# loicpinuela1.net
KiCad netlist of a schematic drawn in Altium Designer
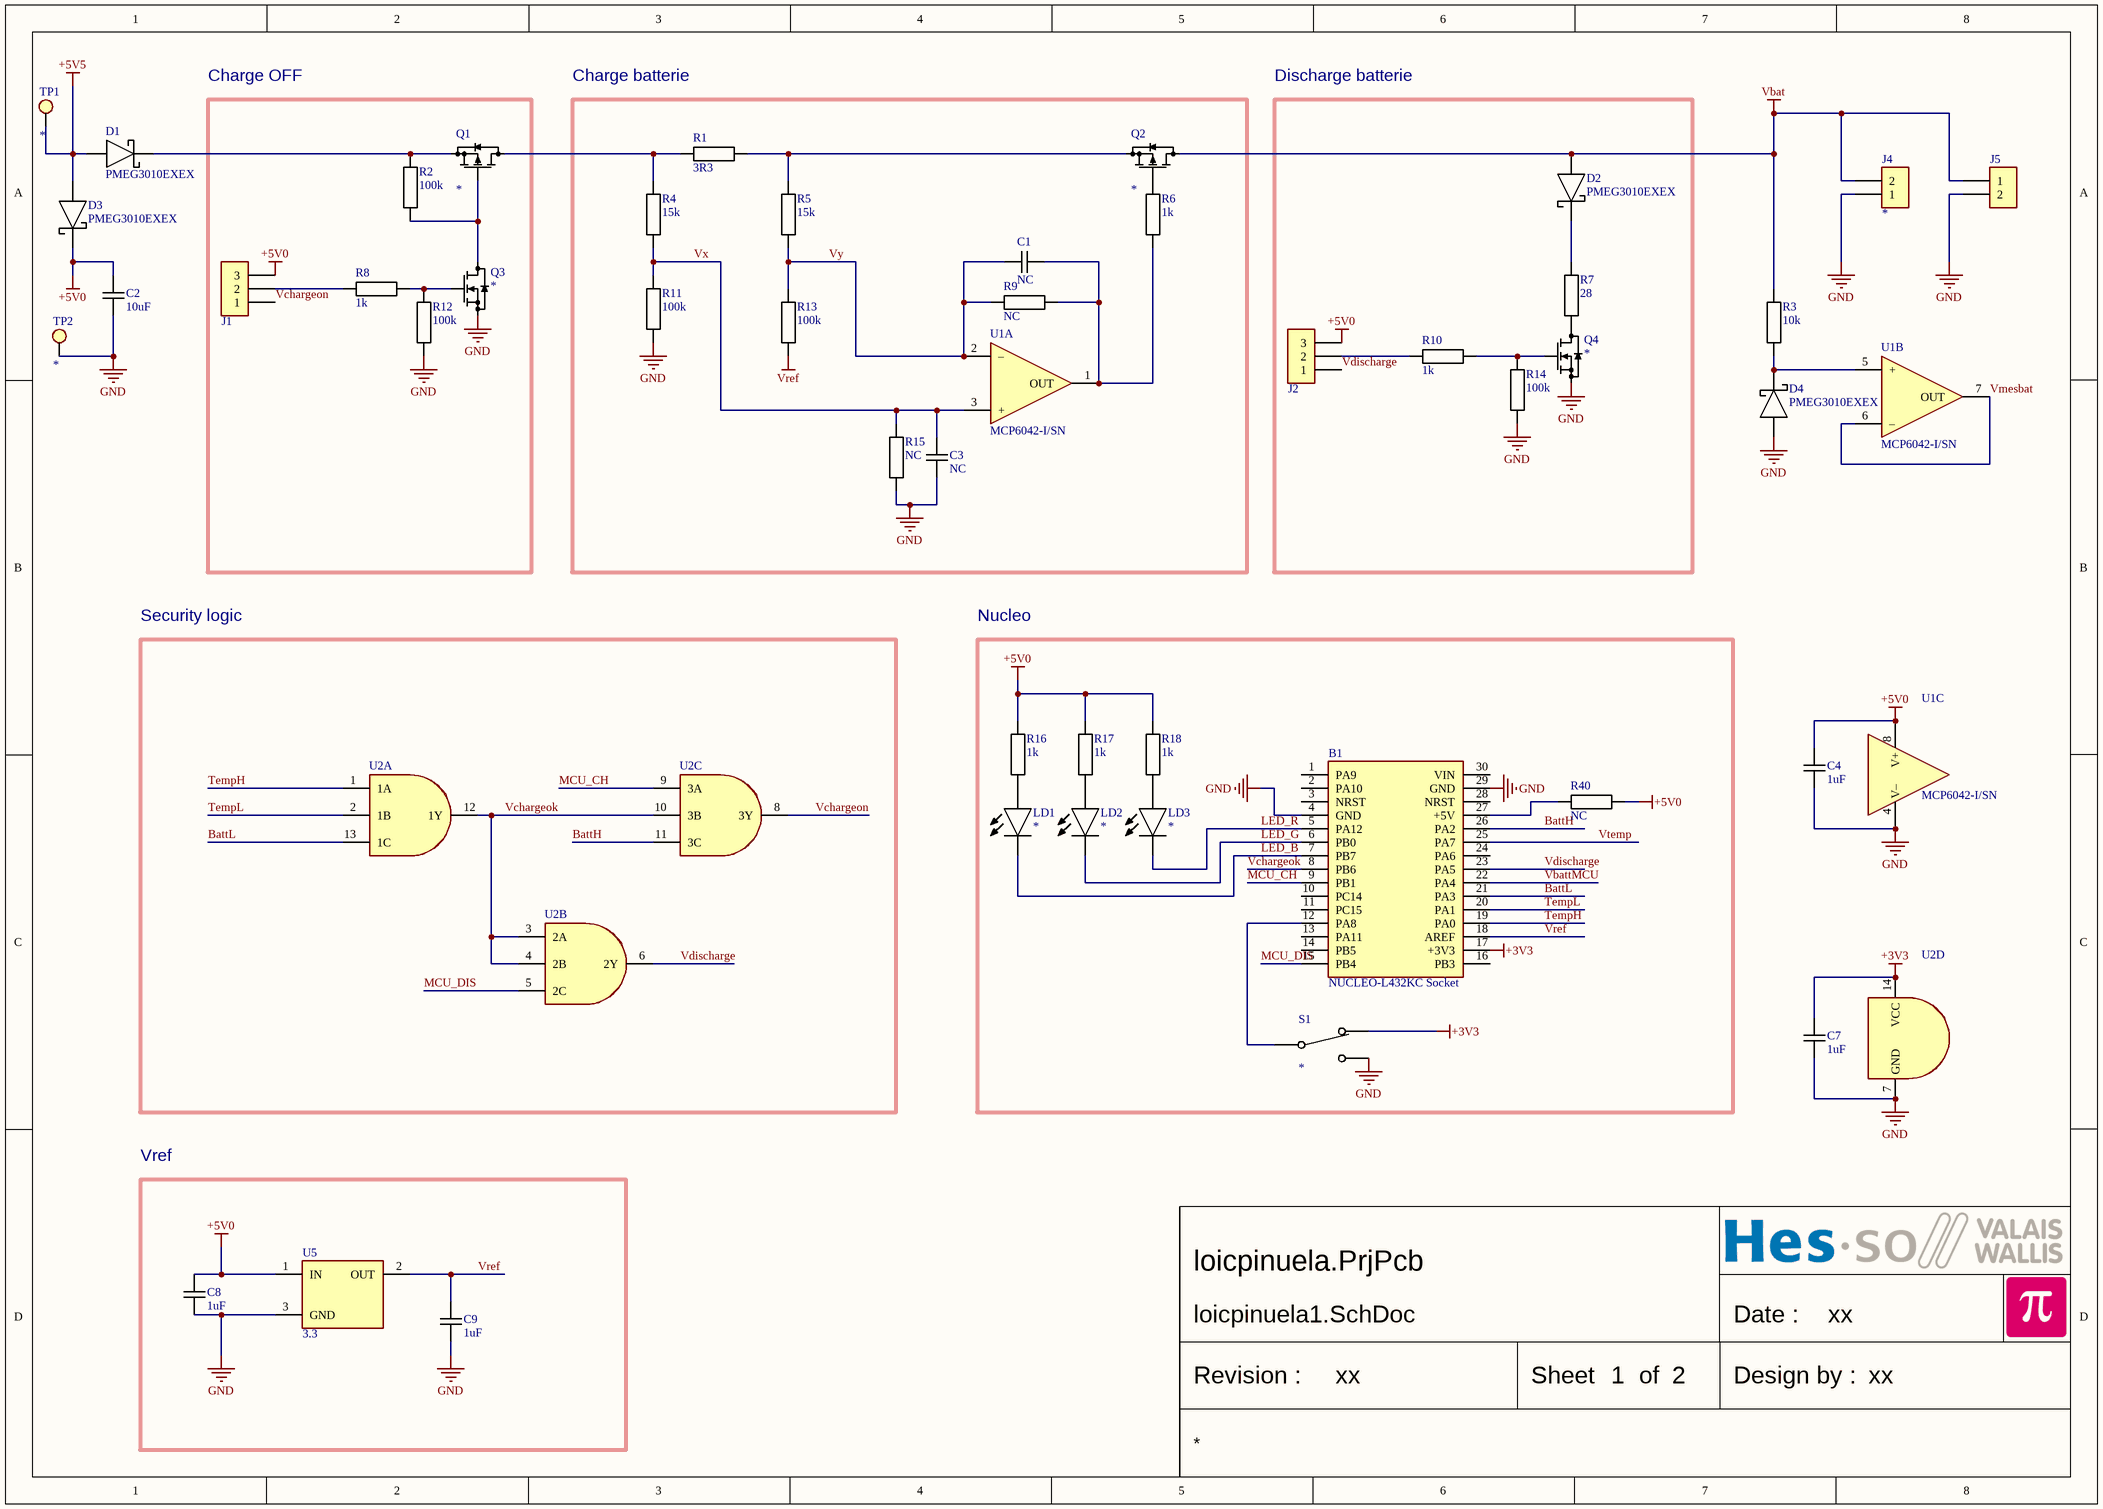
[diagram p0: loicpinuela1.SchDoc]

(export (version "E")
  (design (tool "Eeschema 10.0.6"))
  (components
    (comp (ref "B1")
      (value "NUCLEO-L432KC Socket")
      (footprint "NUCLEO-L432KC Socket")
      (description "ARM Cortex based board")
      (libsource (lib "DevBoard") (part "NUCLEO-L432KC Socket"))
    )
    (comp (ref "C1")
      (value "NC")
      (footprint "CAPACITOR 2012 REFLOW")
      (description "Capacitor")
      (libsource (lib "Capacitor") (part "Capacitor"))
    )
    (comp (ref "C2")
      (value "10uF")
      (footprint "CAPACITOR 2012 REFLOW")
      (description "Capacitor")
      (libsource (lib "Capacitor") (part "Capacitor"))
    )
    (comp (ref "C3")
      (value "NC")
      (footprint "CAPACITOR 2012 REFLOW")
      (description "Capacitor")
      (libsource (lib "Capacitor") (part "Capacitor"))
    )
    (comp (ref "C4")
      (value "1uF")
      (footprint "CAPACITOR 2012 REFLOW")
      (description "Capacitor")
      (libsource (lib "Capacitor") (part "Capacitor"))
    )
    (comp (ref "C7")
      (value "1uF")
      (footprint "CAPACITOR 2012 REFLOW")
      (description "Capacitor")
      (libsource (lib "Capacitor") (part "Capacitor"))
    )
    (comp (ref "C8")
      (value "1uF")
      (footprint "CAPACITOR 2012 REFLOW")
      (description "Capacitor")
      (libsource (lib "Capacitor") (part "Capacitor"))
    )
    (comp (ref "C9")
      (value "1uF")
      (footprint "CAPACITOR 2012 REFLOW")
      (description "Capacitor")
      (libsource (lib "Capacitor") (part "Capacitor"))
    )
    (comp (ref "D1")
      (value "PMEG3010EXEX")
      (footprint "DIODE SOD123-FL REFLOW")
      (description "Diode Schottky generic 2 Leads")
      (libsource (lib "Diode") (part "DIODE SCHOTTKY"))
    )
    (comp (ref "D2")
      (value "PMEG3010EXEX")
      (footprint "DIODE SOD123-FL REFLOW")
      (description "Diode Schottky generic 2 Leads")
      (libsource (lib "Diode") (part "DIODE SCHOTTKY"))
    )
    (comp (ref "D3")
      (value "PMEG3010EXEX")
      (footprint "DIODE SOD123-FL REFLOW")
      (description "Diode Schottky generic 2 Leads")
      (libsource (lib "Diode") (part "DIODE SCHOTTKY"))
    )
    (comp (ref "D4")
      (value "PMEG3010EXEX")
      (footprint "DIODE SOD123-FL REFLOW")
      (description "Diode Schottky generic 2 Leads")
      (libsource (lib "Diode") (part "DIODE SCHOTTKY"))
    )
    (comp (ref "J1")
      (value "*")
      (footprint "PinHeader1x3 P2.54")
      (description "Plug connector")
      (libsource (lib "PinHeader") (part "PinHeader1x3"))
    )
    (comp (ref "J2")
      (value "*")
      (footprint "PinHeader1x3 P2.54")
      (description "Plug connector")
      (libsource (lib "PinHeader") (part "PinHeader1x3"))
    )
    (comp (ref "J4")
      (value "*")
      (footprint "WE 691411810002")
      (description "PCB terminal block")
      (libsource (lib "Header") (part "Header2"))
    )
    (comp (ref "J5")
      (value "~")
      (footprint "Socket1x2 P2.54")
      (description "Receptacle connector")
      (libsource (lib "PinHeader") (part "Socket1x2"))
    )
    (comp (ref "LD1")
      (value "*")
      (footprint "LED 3216 REFLOW")
      (description "LED generic")
      (libsource (lib "Diode") (part "LED"))
    )
    (comp (ref "LD2")
      (value "*")
      (footprint "LED 3216 REFLOW")
      (description "LED generic")
      (libsource (lib "Diode") (part "LED"))
    )
    (comp (ref "LD3")
      (value "*")
      (footprint "LED 3216 REFLOW")
      (description "LED generic")
      (libsource (lib "Diode") (part "LED"))
    )
    (comp (ref "Q1")
      (value "*")
      (footprint "SOT23 P0.95 C1.6x3.0 H1.3")
      (description "Generic MOS-P")
      (libsource (lib "Transistor") (part "MOS-P SOT23 G-S-D"))
    )
    (comp (ref "Q2")
      (value "*")
      (footprint "SOT23 P0.95 C1.6x3.0 H1.3")
      (description "Generic MOS-P")
      (libsource (lib "Transistor") (part "MOS-P SOT23 G-S-D"))
    )
    (comp (ref "Q3")
      (value "*")
      (footprint "SOT23 P0.95 C1.6x3.0 H1.3")
      (description "Generic MOS-N")
      (libsource (lib "Transistor") (part "MOS-N SOT23 G-S-D"))
    )
    (comp (ref "Q4")
      (value "*")
      (footprint "SOT23 P0.95 C1.6x3.0 H1.3")
      (description "Generic MOS-N")
      (libsource (lib "Transistor") (part "MOS-N SOT23 G-S-D"))
    )
    (comp (ref "R1")
      (value "3R3")
      (footprint "RESISTOR 2012 REFLOW")
      (description "Resistor")
      (libsource (lib "Resistor") (part "Resistor"))
    )
    (comp (ref "R2")
      (value "100k")
      (footprint "RESISTOR 2012 REFLOW")
      (description "Resistor")
      (fields (field (name "TOLERANCE") "1%"))
      (libsource (lib "Resistor") (part "Resistor"))
    )
    (comp (ref "R3")
      (value "10k")
      (footprint "RESISTOR 2012 REFLOW")
      (description "Resistor")
      (fields (field (name "TOLERANCE") "1%"))
      (libsource (lib "Resistor") (part "Resistor"))
    )
    (comp (ref "R4")
      (value "15k")
      (footprint "RESISTOR 2012 REFLOW")
      (description "Resistor")
      (fields (field (name "TOLERANCE") "1%"))
      (libsource (lib "Resistor") (part "Resistor"))
    )
    (comp (ref "R5")
      (value "15k")
      (footprint "RESISTOR 2012 REFLOW")
      (description "Resistor")
      (fields (field (name "TOLERANCE") "1%"))
      (libsource (lib "Resistor") (part "Resistor"))
    )
    (comp (ref "R6")
      (value "1k")
      (footprint "RESISTOR 2012 REFLOW")
      (description "Resistor")
      (fields (field (name "TOLERANCE") "1%"))
      (libsource (lib "Resistor") (part "Resistor"))
    )
    (comp (ref "R7")
      (value "28")
      (footprint "RESISTOR 2012 REFLOW")
      (description "Resistor")
      (fields (field (name "TOLERANCE") "1%"))
      (libsource (lib "Resistor") (part "Resistor"))
    )
    (comp (ref "R8")
      (value "1k")
      (footprint "RESISTOR 2012 REFLOW")
      (description "Resistor")
      (fields (field (name "TOLERANCE") "1%"))
      (libsource (lib "Resistor") (part "Resistor"))
    )
    (comp (ref "R9")
      (value "NC")
      (footprint "RESISTOR 2012 REFLOW")
      (description "Resistor")
      (libsource (lib "Resistor") (part "Resistor"))
    )
    (comp (ref "R10")
      (value "1k")
      (footprint "RESISTOR 2012 REFLOW")
      (description "Resistor")
      (fields (field (name "TOLERANCE") "1%"))
      (libsource (lib "Resistor") (part "Resistor"))
    )
    (comp (ref "R11")
      (value "100k")
      (footprint "RESISTOR 2012 REFLOW")
      (description "Resistor")
      (fields (field (name "TOLERANCE") "1%"))
      (libsource (lib "Resistor") (part "Resistor"))
    )
    (comp (ref "R12")
      (value "100k")
      (footprint "RESISTOR 2012 REFLOW")
      (description "Resistor")
      (fields (field (name "TOLERANCE") "1%"))
      (libsource (lib "Resistor") (part "Resistor"))
    )
    (comp (ref "R13")
      (value "100k")
      (footprint "RESISTOR 2012 REFLOW")
      (description "Resistor")
      (fields (field (name "TOLERANCE") "1%"))
      (libsource (lib "Resistor") (part "Resistor"))
    )
    (comp (ref "R14")
      (value "100k")
      (footprint "RESISTOR 2012 REFLOW")
      (description "Resistor")
      (fields (field (name "TOLERANCE") "1%"))
      (libsource (lib "Resistor") (part "Resistor"))
    )
    (comp (ref "R15")
      (value "NC")
      (footprint "RESISTOR 2012 REFLOW")
      (description "Resistor")
      (libsource (lib "Resistor") (part "Resistor"))
    )
    (comp (ref "R16")
      (value "1k")
      (footprint "RESISTOR 2012 REFLOW")
      (description "Resistor")
      (fields (field (name "TOLERANCE") "1%"))
      (libsource (lib "Resistor") (part "Resistor"))
    )
    (comp (ref "R17")
      (value "1k")
      (footprint "RESISTOR 2012 REFLOW")
      (description "Resistor")
      (fields (field (name "TOLERANCE") "1%"))
      (libsource (lib "Resistor") (part "Resistor"))
    )
    (comp (ref "R18")
      (value "1k")
      (footprint "RESISTOR 2012 REFLOW")
      (description "Resistor")
      (fields (field (name "TOLERANCE") "1%"))
      (libsource (lib "Resistor") (part "Resistor"))
    )
    (comp (ref "R40")
      (value "NC")
      (footprint "RESISTOR 2012 REFLOW")
      (description "Resistor")
      (libsource (lib "Resistor") (part "Resistor"))
    )
    (comp (ref "S1")
      (value "*")
      (footprint "SLIDE SWITCH Knitter MFP120")
      (description "Slide Switch 1Pole ON-ON")
      (fields (field (name "ALTIUM_VALUE") "*"))
      (libsource (lib "Button") (part "Slide Switch 1Pole ON-ON"))
    )
    (comp (ref "TP1")
      (value "*")
      (footprint "Hole 0.8 D1.5")
      (description "Hole")
      (libsource (lib "Testpoint") (part "Hole"))
    )
    (comp (ref "TP2")
      (value "*")
      (footprint "Hole 0.8 D1.5")
      (description "Hole")
      (libsource (lib "Testpoint") (part "Hole"))
    )
    (comp (ref "U1")
      (value "MCP6042-I/SN")
      (footprint "SO8 P1.27 C4.0X5.0 H1.75")
      (description "Generic dual OPA 8 pins")
      (libsource (lib "Amplifier") (part "OPA DUAL"))
    )
    (comp (ref "U2")
      (value "~")
      (footprint "SO14 P1.27 C4.0X8.8 H1.75")
      (description "GATE AND 3X  TRIPLE INPUT 14P")
      (libsource (lib "IntegratedCircuit") (part "GATE AND 3X  TRIPLE INPUT 14P"))
    )
    (comp (ref "U5")
      (value "3.3")
      (footprint "SOT23 P0.95 C1.6x3.0 H1.3")
      (description "Generic Positive Voltage Reference")
      (libsource (lib "Regulator") (part "REFERENCE SOT23 IN,OUT,GND"))
    )
  )
  (nets
    (net (code "1") (name "+3V3") (class "Default")
      (node (ref "B1") (pin "17") (pinfunction "+3V3_17") (pintype "passive"))
      (node (ref "C7") (pin "2") (pinfunction "2_2") (pintype "passive"))
      (node (ref "S1") (pin "1") (pinfunction "NC_1") (pintype "passive"))
      (node (ref "U2") (pin "14") (pinfunction "VCC_14") (pintype "passive"))
    )
    (net (code "2") (name "+5V0") (class "Default")
      (node (ref "C2") (pin "2") (pinfunction "2_2") (pintype "passive"))
      (node (ref "C4") (pin "2") (pinfunction "2_2") (pintype "passive"))
      (node (ref "C8") (pin "2") (pinfunction "2_2") (pintype "passive"))
      (node (ref "D3") (pin "1") (pinfunction "C_1") (pintype "passive"))
      (node (ref "J1") (pin "3") (pinfunction "3_3") (pintype "passive"))
      (node (ref "J2") (pin "3") (pinfunction "3_3") (pintype "passive"))
      (node (ref "R16") (pin "2") (pinfunction "2_2") (pintype "passive"))
      (node (ref "R17") (pin "2") (pinfunction "2_2") (pintype "passive"))
      (node (ref "R18") (pin "2") (pinfunction "2_2") (pintype "passive"))
      (node (ref "R40") (pin "1") (pinfunction "1_1") (pintype "passive"))
      (node (ref "U1") (pin "8") (pinfunction "V+_8") (pintype "passive"))
      (node (ref "U5") (pin "1") (pinfunction "IN_1") (pintype "passive"))
    )
    (net (code "3") (name "+5V5") (class "Default")
      (node (ref "D1") (pin "2") (pinfunction "A_2") (pintype "passive"))
      (node (ref "D3") (pin "2") (pinfunction "A_2") (pintype "passive"))
      (node (ref "TP1") (pin "1") (pinfunction "1_1") (pintype "passive"))
    )
    (net (code "4") (name "/BattH") (class "Default")
      (node (ref "B1") (pin "26") (pinfunction "PA2_26") (pintype "passive"))
      (node (ref "U2") (pin "11") (pinfunction "3C_11") (pintype "passive"))
    )
    (net (code "5") (name "/BattL") (class "Default")
      (node (ref "B1") (pin "21") (pinfunction "PA3_21") (pintype "passive"))
      (node (ref "U2") (pin "13") (pinfunction "1C_13") (pintype "passive"))
    )
    (net (code "6") (name "/LED_B") (class "Default")
      (node (ref "B1") (pin "7") (pinfunction "PB7_7") (pintype "passive"))
      (node (ref "LD1") (pin "1") (pinfunction "C_1") (pintype "passive"))
    )
    (net (code "7") (name "/LED_G") (class "Default")
      (node (ref "B1") (pin "6") (pinfunction "PB0_6") (pintype "passive"))
      (node (ref "LD2") (pin "1") (pinfunction "C_1") (pintype "passive"))
    )
    (net (code "8") (name "/LED_R") (class "Default")
      (node (ref "B1") (pin "5") (pinfunction "PA12_5") (pintype "passive"))
      (node (ref "LD3") (pin "1") (pinfunction "C_1") (pintype "passive"))
    )
    (net (code "9") (name "/MCU_CH") (class "Default")
      (node (ref "B1") (pin "9") (pinfunction "PB1_9") (pintype "passive"))
      (node (ref "U2") (pin "9") (pinfunction "3A_9") (pintype "passive"))
    )
    (net (code "10") (name "/MCU_DIS") (class "Default")
      (node (ref "B1") (pin "15") (pinfunction "PB4_15") (pintype "passive"))
      (node (ref "U2") (pin "5") (pinfunction "2C_5") (pintype "passive"))
    )
    (net (code "11") (name "/TempH") (class "Default")
      (node (ref "B1") (pin "19") (pinfunction "PA0_19") (pintype "passive"))
      (node (ref "U2") (pin "1") (pinfunction "1A_1") (pintype "passive"))
    )
    (net (code "12") (name "/TempL") (class "Default")
      (node (ref "B1") (pin "20") (pinfunction "PA1_20") (pintype "passive"))
      (node (ref "U2") (pin "2") (pinfunction "1B_2") (pintype "passive"))
    )
    (net (code "13") (name "/VbattMCU") (class "Default")
      (node (ref "B1") (pin "22") (pinfunction "PA4_22") (pintype "passive"))
    )
    (net (code "14") (name "/Vchargeok") (class "Default")
      (node (ref "B1") (pin "8") (pinfunction "PB6_8") (pintype "passive"))
      (node (ref "U2") (pin "10") (pinfunction "3B_10") (pintype "passive"))
      (node (ref "U2") (pin "12") (pinfunction "1Y_12") (pintype "passive"))
      (node (ref "U2") (pin "3") (pinfunction "2A_3") (pintype "passive"))
      (node (ref "U2") (pin "4") (pinfunction "2B_4") (pintype "passive"))
    )
    (net (code "15") (name "/Vchargeon") (class "Default")
      (node (ref "J1") (pin "1") (pinfunction "1_1") (pintype "passive"))
      (node (ref "U2") (pin "8") (pinfunction "3Y_8") (pintype "passive"))
    )
    (net (code "16") (name "/Vdischarge") (class "Default")
      (node (ref "B1") (pin "23") (pinfunction "PA5_23") (pintype "passive"))
      (node (ref "J2") (pin "1") (pinfunction "1_1") (pintype "passive"))
      (node (ref "U2") (pin "6") (pinfunction "2Y_6") (pintype "passive"))
    )
    (net (code "17") (name "/Vmesbat") (class "Default")
      (node (ref "U1") (pin "6") (pinfunction "–_6") (pintype "passive"))
      (node (ref "U1") (pin "7") (pinfunction "OUT_7") (pintype "passive"))
    )
    (net (code "18") (name "/Vtemp") (class "Default")
      (node (ref "B1") (pin "25") (pinfunction "PA7_25") (pintype "passive"))
    )
    (net (code "19") (name "/Vx") (class "Default")
      (node (ref "C3") (pin "2") (pinfunction "2_2") (pintype "passive"))
      (node (ref "R11") (pin "2") (pinfunction "2_2") (pintype "passive"))
      (node (ref "R15") (pin "2") (pinfunction "2_2") (pintype "passive"))
      (node (ref "R4") (pin "1") (pinfunction "1_1") (pintype "passive"))
      (node (ref "U1") (pin "3") (pinfunction "+_3") (pintype "passive"))
    )
    (net (code "20") (name "/Vy") (class "Default")
      (node (ref "C1") (pin "2") (pinfunction "2_2") (pintype "passive"))
      (node (ref "R13") (pin "2") (pinfunction "2_2") (pintype "passive"))
      (node (ref "R5") (pin "1") (pinfunction "1_1") (pintype "passive"))
      (node (ref "R9") (pin "2") (pinfunction "2_2") (pintype "passive"))
      (node (ref "U1") (pin "2") (pinfunction "–_2") (pintype "passive"))
    )
    (net (code "21") (name "GND") (class "Default")
      (node (ref "B1") (pin "29") (pinfunction "GND_29") (pintype "passive"))
      (node (ref "B1") (pin "4") (pinfunction "GND_4") (pintype "passive"))
      (node (ref "C2") (pin "1") (pinfunction "1_1") (pintype "passive"))
      (node (ref "C3") (pin "1") (pinfunction "1_1") (pintype "passive"))
      (node (ref "C4") (pin "1") (pinfunction "1_1") (pintype "passive"))
      (node (ref "C7") (pin "1") (pinfunction "1_1") (pintype "passive"))
      (node (ref "C8") (pin "1") (pinfunction "1_1") (pintype "passive"))
      (node (ref "C9") (pin "1") (pinfunction "1_1") (pintype "passive"))
      (node (ref "D4") (pin "2") (pinfunction "A_2") (pintype "passive"))
      (node (ref "J4") (pin "1") (pinfunction "1_1") (pintype "passive"))
      (node (ref "J5") (pin "2") (pinfunction "2_2") (pintype "passive"))
      (node (ref "Q3") (pin "2") (pinfunction "S_2") (pintype "passive"))
      (node (ref "Q4") (pin "2") (pinfunction "S_2") (pintype "passive"))
      (node (ref "R11") (pin "1") (pinfunction "1_1") (pintype "passive"))
      (node (ref "R12") (pin "1") (pinfunction "1_1") (pintype "passive"))
      (node (ref "R14") (pin "1") (pinfunction "1_1") (pintype "passive"))
      (node (ref "R15") (pin "1") (pinfunction "1_1") (pintype "passive"))
      (node (ref "S1") (pin "3") (pinfunction "NO_3") (pintype "passive"))
      (node (ref "TP2") (pin "1") (pinfunction "1_1") (pintype "passive"))
      (node (ref "U1") (pin "4") (pinfunction "V–_4") (pintype "passive"))
      (node (ref "U2") (pin "7") (pinfunction "GND_7") (pintype "passive"))
      (node (ref "U5") (pin "3") (pinfunction "GND_3") (pintype "passive"))
    )
    (net (code "22") (name "Net-(B1-+5V)") (class "Default")
      (node (ref "B1") (pin "27") (pinfunction "+5V_27") (pintype "passive"))
      (node (ref "R40") (pin "2") (pinfunction "2_2") (pintype "passive"))
    )
    (net (code "23") (name "Net-(B1-PA8)") (class "Default")
      (node (ref "B1") (pin "12") (pinfunction "PA8_12") (pintype "passive"))
      (node (ref "S1") (pin "2") (pinfunction "com_2") (pintype "passive"))
    )
    (net (code "24") (name "Net-(D1-C)") (class "Default")
      (node (ref "D1") (pin "1") (pinfunction "C_1") (pintype "passive"))
      (node (ref "Q1") (pin "2") (pinfunction "S_2") (pintype "passive"))
      (node (ref "R2") (pin "2") (pinfunction "2_2") (pintype "passive"))
    )
    (net (code "25") (name "Net-(D2-C)") (class "Default")
      (node (ref "D2") (pin "1") (pinfunction "C_1") (pintype "passive"))
      (node (ref "R7") (pin "2") (pinfunction "2_2") (pintype "passive"))
    )
    (net (code "26") (name "Net-(D4-C)") (class "Default")
      (node (ref "D4") (pin "1") (pinfunction "C_1") (pintype "passive"))
      (node (ref "R3") (pin "1") (pinfunction "1_1") (pintype "passive"))
      (node (ref "U1") (pin "5") (pinfunction "+_5") (pintype "passive"))
    )
    (net (code "27") (name "Net-(J1-Pad2)") (class "Default")
      (node (ref "J1") (pin "2") (pinfunction "2_2") (pintype "passive"))
      (node (ref "R8") (pin "1") (pinfunction "1_1") (pintype "passive"))
    )
    (net (code "28") (name "Net-(J2-Pad2)") (class "Default")
      (node (ref "J2") (pin "2") (pinfunction "2_2") (pintype "passive"))
      (node (ref "R10") (pin "1") (pinfunction "1_1") (pintype "passive"))
    )
    (net (code "29") (name "Net-(LD1-A)") (class "Default")
      (node (ref "LD1") (pin "2") (pinfunction "A_2") (pintype "passive"))
      (node (ref "R16") (pin "1") (pinfunction "1_1") (pintype "passive"))
    )
    (net (code "30") (name "Net-(LD2-A)") (class "Default")
      (node (ref "LD2") (pin "2") (pinfunction "A_2") (pintype "passive"))
      (node (ref "R17") (pin "1") (pinfunction "1_1") (pintype "passive"))
    )
    (net (code "31") (name "Net-(LD3-A)") (class "Default")
      (node (ref "LD3") (pin "2") (pinfunction "A_2") (pintype "passive"))
      (node (ref "R18") (pin "1") (pinfunction "1_1") (pintype "passive"))
    )
    (net (code "32") (name "Net-(Q1-D)") (class "Default")
      (node (ref "Q1") (pin "3") (pinfunction "D_3") (pintype "passive"))
      (node (ref "R1") (pin "1") (pinfunction "1_1") (pintype "passive"))
      (node (ref "R4") (pin "2") (pinfunction "2_2") (pintype "passive"))
    )
    (net (code "33") (name "Net-(Q1-G)") (class "Default")
      (node (ref "Q1") (pin "1") (pinfunction "G_1") (pintype "passive"))
      (node (ref "Q3") (pin "3") (pinfunction "D_3") (pintype "passive"))
      (node (ref "R2") (pin "1") (pinfunction "1_1") (pintype "passive"))
    )
    (net (code "34") (name "Net-(Q2-G)") (class "Default")
      (node (ref "Q2") (pin "1") (pinfunction "G_1") (pintype "passive"))
      (node (ref "R6") (pin "2") (pinfunction "2_2") (pintype "passive"))
    )
    (net (code "35") (name "Net-(Q2-S)") (class "Default")
      (node (ref "Q2") (pin "2") (pinfunction "S_2") (pintype "passive"))
      (node (ref "R1") (pin "2") (pinfunction "2_2") (pintype "passive"))
      (node (ref "R5") (pin "2") (pinfunction "2_2") (pintype "passive"))
    )
    (net (code "36") (name "Net-(Q3-G)") (class "Default")
      (node (ref "Q3") (pin "1") (pinfunction "G_1") (pintype "passive"))
      (node (ref "R12") (pin "2") (pinfunction "2_2") (pintype "passive"))
      (node (ref "R8") (pin "2") (pinfunction "2_2") (pintype "passive"))
    )
    (net (code "37") (name "Net-(Q4-D)") (class "Default")
      (node (ref "Q4") (pin "3") (pinfunction "D_3") (pintype "passive"))
      (node (ref "R7") (pin "1") (pinfunction "1_1") (pintype "passive"))
    )
    (net (code "38") (name "Net-(Q4-G)") (class "Default")
      (node (ref "Q4") (pin "1") (pinfunction "G_1") (pintype "passive"))
      (node (ref "R10") (pin "2") (pinfunction "2_2") (pintype "passive"))
      (node (ref "R14") (pin "2") (pinfunction "2_2") (pintype "passive"))
    )
    (net (code "39") (name "Net-(U1A-OUT)") (class "Default")
      (node (ref "C1") (pin "1") (pinfunction "1_1") (pintype "passive"))
      (node (ref "R6") (pin "1") (pinfunction "1_1") (pintype "passive"))
      (node (ref "R9") (pin "1") (pinfunction "1_1") (pintype "passive"))
      (node (ref "U1") (pin "1") (pinfunction "OUT_1") (pintype "passive"))
    )
    (net (code "40") (name "Vbat") (class "Default")
      (node (ref "D2") (pin "2") (pinfunction "A_2") (pintype "passive"))
      (node (ref "J4") (pin "2") (pinfunction "2_2") (pintype "passive"))
      (node (ref "J5") (pin "1") (pinfunction "1_1") (pintype "passive"))
      (node (ref "Q2") (pin "3") (pinfunction "D_3") (pintype "passive"))
      (node (ref "R3") (pin "2") (pinfunction "2_2") (pintype "passive"))
    )
    (net (code "41") (name "Vref") (class "Default")
      (node (ref "B1") (pin "18") (pinfunction "AREF_18") (pintype "passive"))
      (node (ref "C9") (pin "2") (pinfunction "2_2") (pintype "passive"))
      (node (ref "R13") (pin "1") (pinfunction "1_1") (pintype "passive"))
      (node (ref "U5") (pin "2") (pinfunction "OUT_2") (pintype "passive"))
    )
    (net (code "42") (name "unconnected-(B1-NRST-Pad3)") (class "Default")
      (node (ref "B1") (pin "3") (pinfunction "NRST_3") (pintype "passive"))
    )
    (net (code "43") (name "unconnected-(B1-NRST-Pad28)") (class "Default")
      (node (ref "B1") (pin "28") (pinfunction "NRST_28") (pintype "passive"))
    )
    (net (code "44") (name "unconnected-(B1-PA6-Pad24)") (class "Default")
      (node (ref "B1") (pin "24") (pinfunction "PA6_24") (pintype "passive"))
    )
    (net (code "45") (name "unconnected-(B1-PA9-Pad1)") (class "Default")
      (node (ref "B1") (pin "1") (pinfunction "PA9_1") (pintype "passive"))
    )
    (net (code "46") (name "unconnected-(B1-PA10-Pad2)") (class "Default")
      (node (ref "B1") (pin "2") (pinfunction "PA10_2") (pintype "passive"))
    )
    (net (code "47") (name "unconnected-(B1-PA11-Pad13)") (class "Default")
      (node (ref "B1") (pin "13") (pinfunction "PA11_13") (pintype "passive"))
    )
    (net (code "48") (name "unconnected-(B1-PB3-Pad16)") (class "Default")
      (node (ref "B1") (pin "16") (pinfunction "PB3_16") (pintype "passive"))
    )
    (net (code "49") (name "unconnected-(B1-PB5-Pad14)") (class "Default")
      (node (ref "B1") (pin "14") (pinfunction "PB5_14") (pintype "passive"))
    )
    (net (code "50") (name "unconnected-(B1-PC14-Pad10)") (class "Default")
      (node (ref "B1") (pin "10") (pinfunction "PC14_10") (pintype "passive"))
    )
    (net (code "51") (name "unconnected-(B1-PC15-Pad11)") (class "Default")
      (node (ref "B1") (pin "11") (pinfunction "PC15_11") (pintype "passive"))
    )
    (net (code "52") (name "unconnected-(B1-VIN-Pad30)") (class "Default")
      (node (ref "B1") (pin "30") (pinfunction "VIN_30") (pintype "passive"))
    )
  )
)
